# SCH_Business-card-2_2024-04-09.net
KiCad netlist of a schematic drawn in EasyEDA
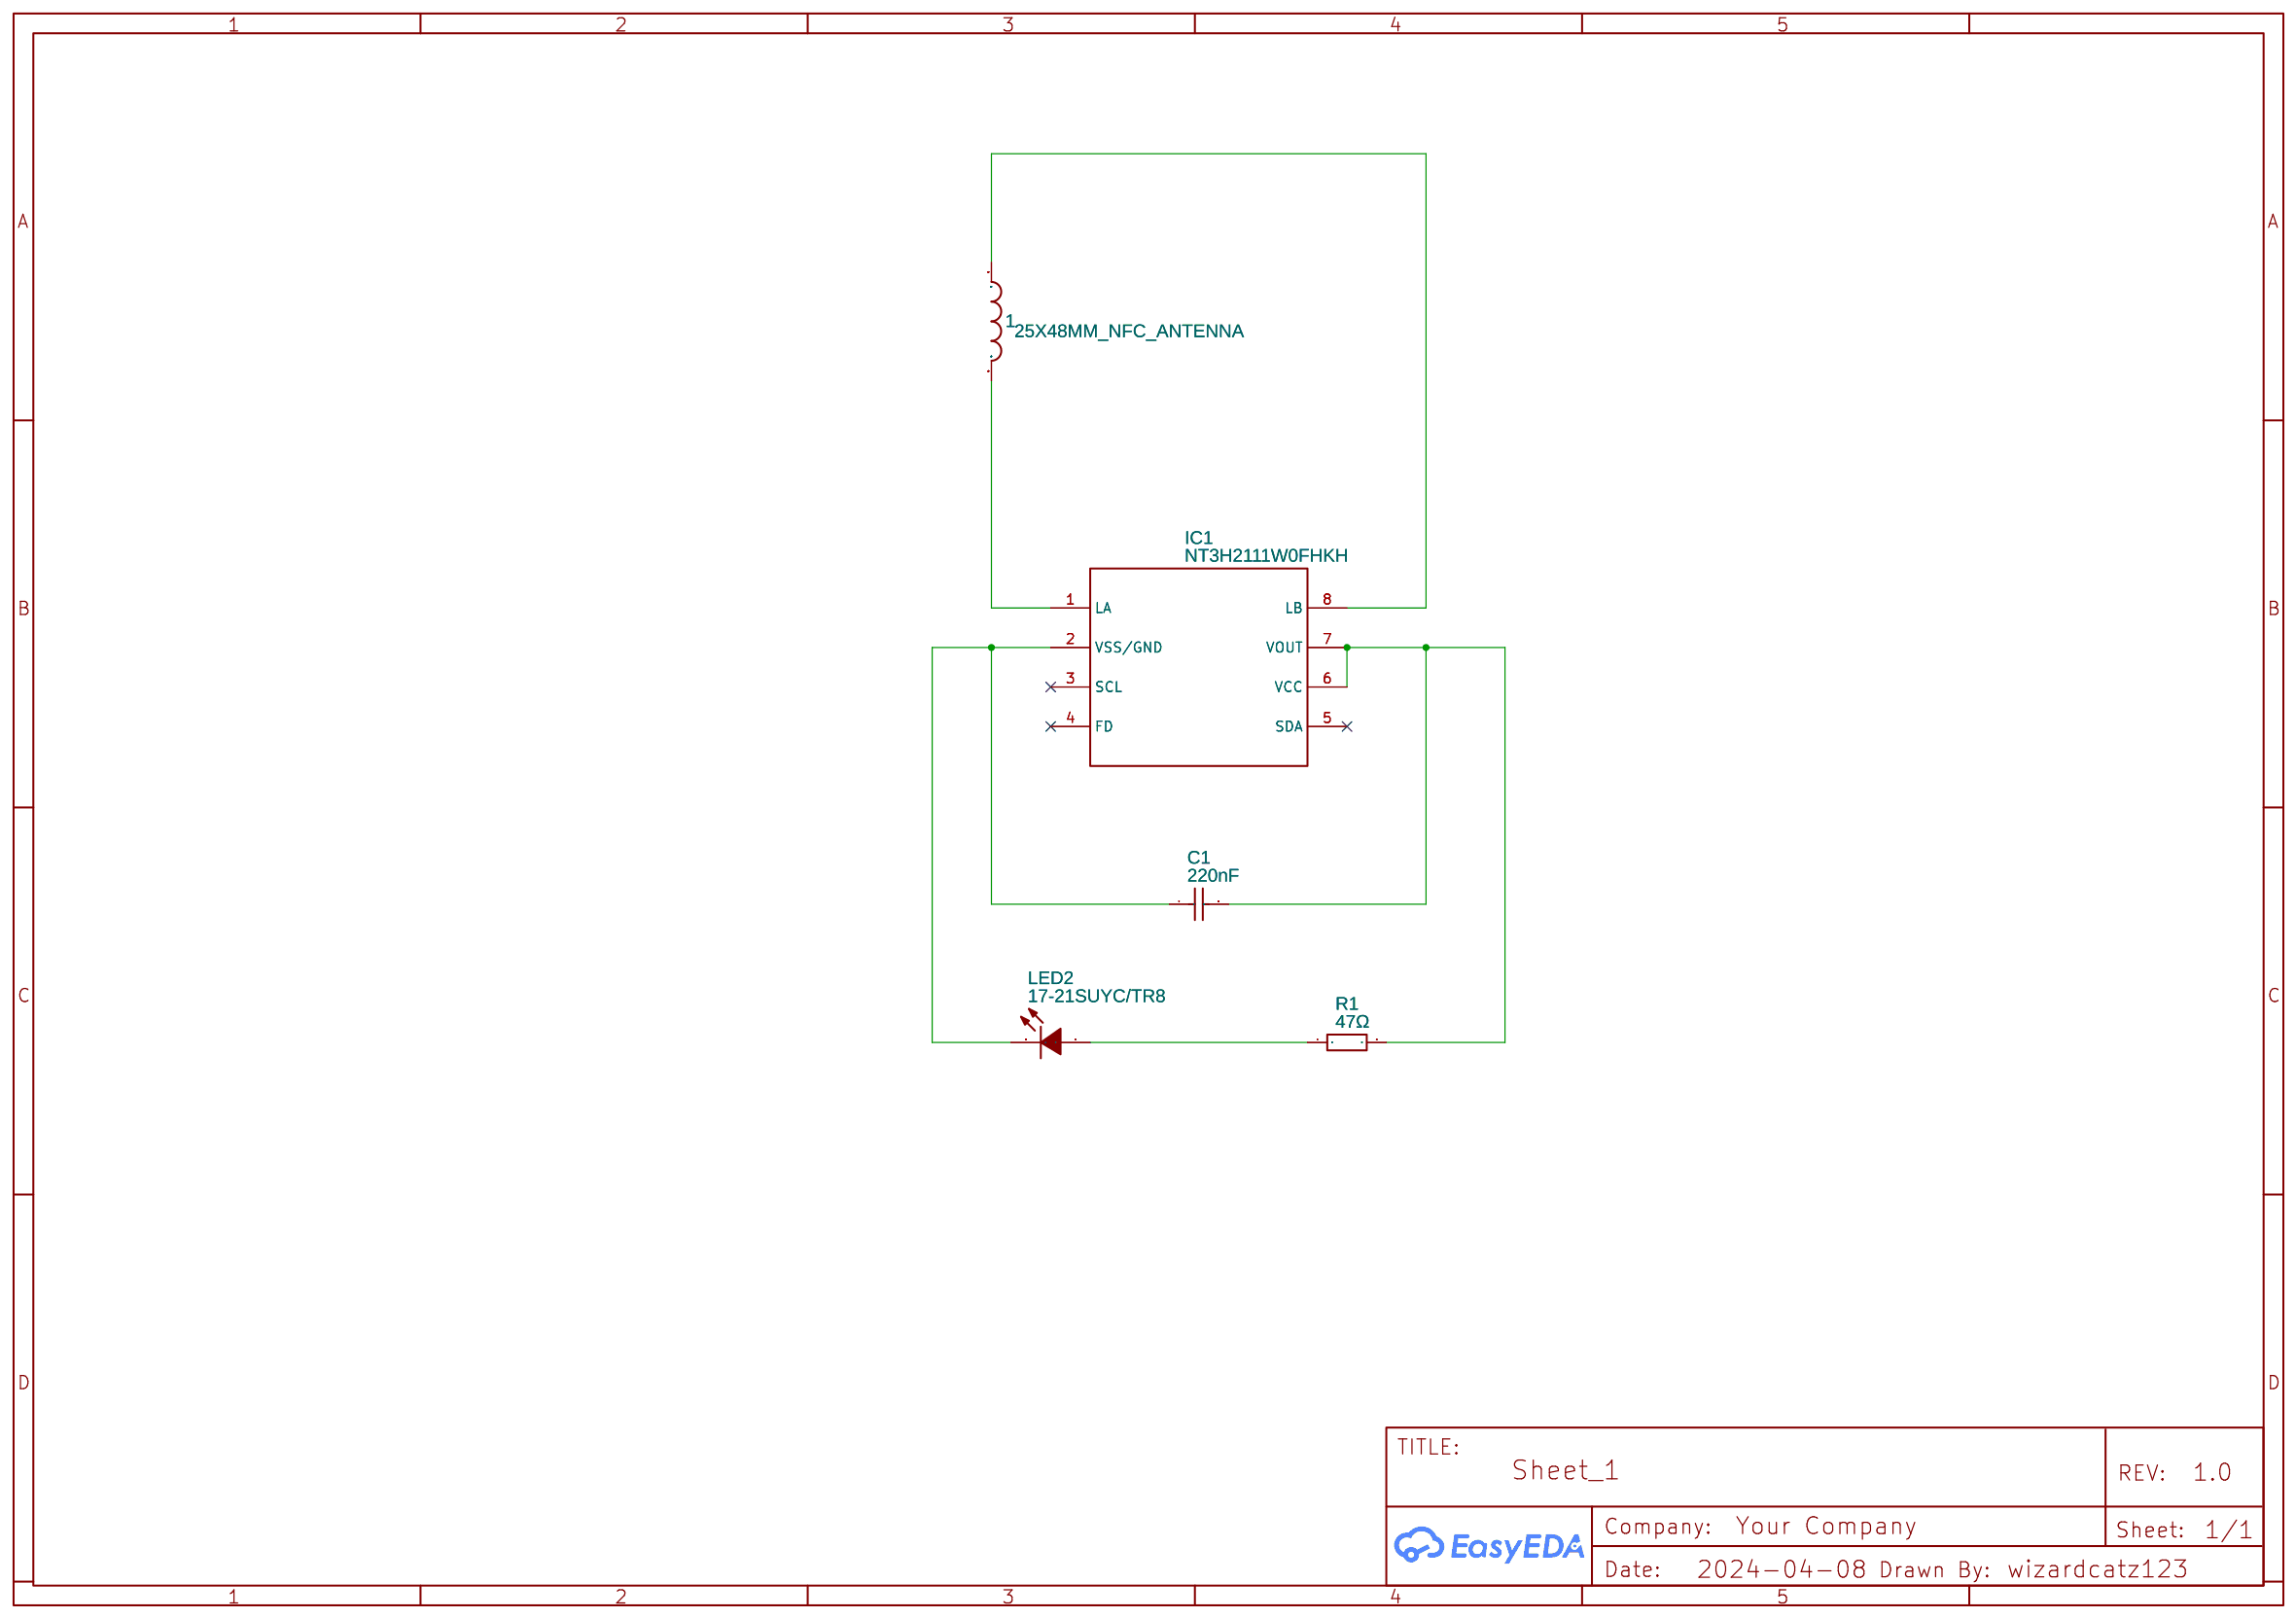
[diagram p0: schematic sheet]

(export (version "E")
  (design (tool "Eeschema 10.0.6"))
  (components
    (comp (ref "1") (value "25X48MM_NFC_ANTENNA") (libsource (lib "") (part "25X48MM_NFC_ANTENNA")))
    (comp (ref "C1")
      (value "220nF")
      (fields (field (name "Manufacturer Part") "CL10B224KA8NNNC") (field (name "Manufacturer") "SAMSUNG"))
      (libsource (lib "") (part "0603C-220nF_CL10B224KA8NNNC"))
    )
    (comp (ref "IC1") (value "NT3H2111W0FHKH") (libsource (lib "") (part "NT3H2111W0FHKH")))
    (comp (ref "LED2")
      (value "17-21SUYC/TR8")
      (fields (field (name "Manufacturer Part") "KT-0805黄灯") (field (name "Manufacturer") "KENTO"))
      (libsource (lib "") (part "17-21SUYC/TR8"))
    )
    (comp (ref "R1")
      (value "47Ω")
      (fields
        (field (name "Manufacturer Part") "0603WAF470JT5E")
        (field (name "Manufacturer") "UNI-ROYAL(厚声)")
      )
      (libsource (lib "") (part "0603WAF470JT5E"))
    )
  )
  (nets
    (net (code "1") (name "Net-(IC1-LA)") (class "Default")
      (node (ref "1") (pin "P$2") (pinfunction "P$2_P$2") (pintype "bidirectional"))
      (node (ref "IC1") (pin "1") (pinfunction "LA_1") (pintype "unspecified"))
    )
    (net (code "2") (name "Net-(IC1-LB)") (class "Default")
      (node (ref "1") (pin "P$1") (pinfunction "P$1_P$1") (pintype "bidirectional"))
      (node (ref "IC1") (pin "8") (pinfunction "LB_8") (pintype "unspecified"))
    )
    (net (code "3") (name "Net-(IC1-VCC)") (class "Default")
      (node (ref "C1") (pin "2") (pinfunction "2_2") (pintype "input"))
      (node (ref "IC1") (pin "6") (pinfunction "VCC_6") (pintype "passive"))
      (node (ref "IC1") (pin "7") (pinfunction "VOUT_7") (pintype "passive"))
      (node (ref "R1") (pin "2") (pinfunction "2_2") (pintype "input"))
    )
    (net (code "4") (name "Net-(IC1-VSS{slash}GND)") (class "Default")
      (node (ref "C1") (pin "1") (pinfunction "1_1") (pintype "input"))
      (node (ref "IC1") (pin "2") (pinfunction "VSS/GND_2") (pintype "unspecified"))
      (node (ref "LED2") (pin "2") (pinfunction "-_2") (pintype "unspecified"))
    )
    (net (code "5") (name "Net-(LED2-+)") (class "Default")
      (node (ref "LED2") (pin "1") (pinfunction "+_1") (pintype "unspecified"))
      (node (ref "R1") (pin "1") (pinfunction "1_1") (pintype "input"))
    )
    (net (code "6") (name "unconnected-(IC1-FD-Pad4)") (class "Default")
      (node (ref "IC1") (pin "4") (pinfunction "FD_4") (pintype "unspecified+no_connect"))
    )
    (net (code "7") (name "unconnected-(IC1-SCL-Pad3)") (class "Default")
      (node (ref "IC1") (pin "3") (pinfunction "SCL_3") (pintype "unspecified+no_connect"))
    )
    (net (code "8") (name "unconnected-(IC1-SDA-Pad5)") (class "Default")
      (node (ref "IC1") (pin "5") (pinfunction "SDA_5") (pintype "unspecified+no_connect"))
    )
  )
)
